# P11_RS2-32_RS-485.net
KiCad netlist of a schematic drawn in Altium Designer
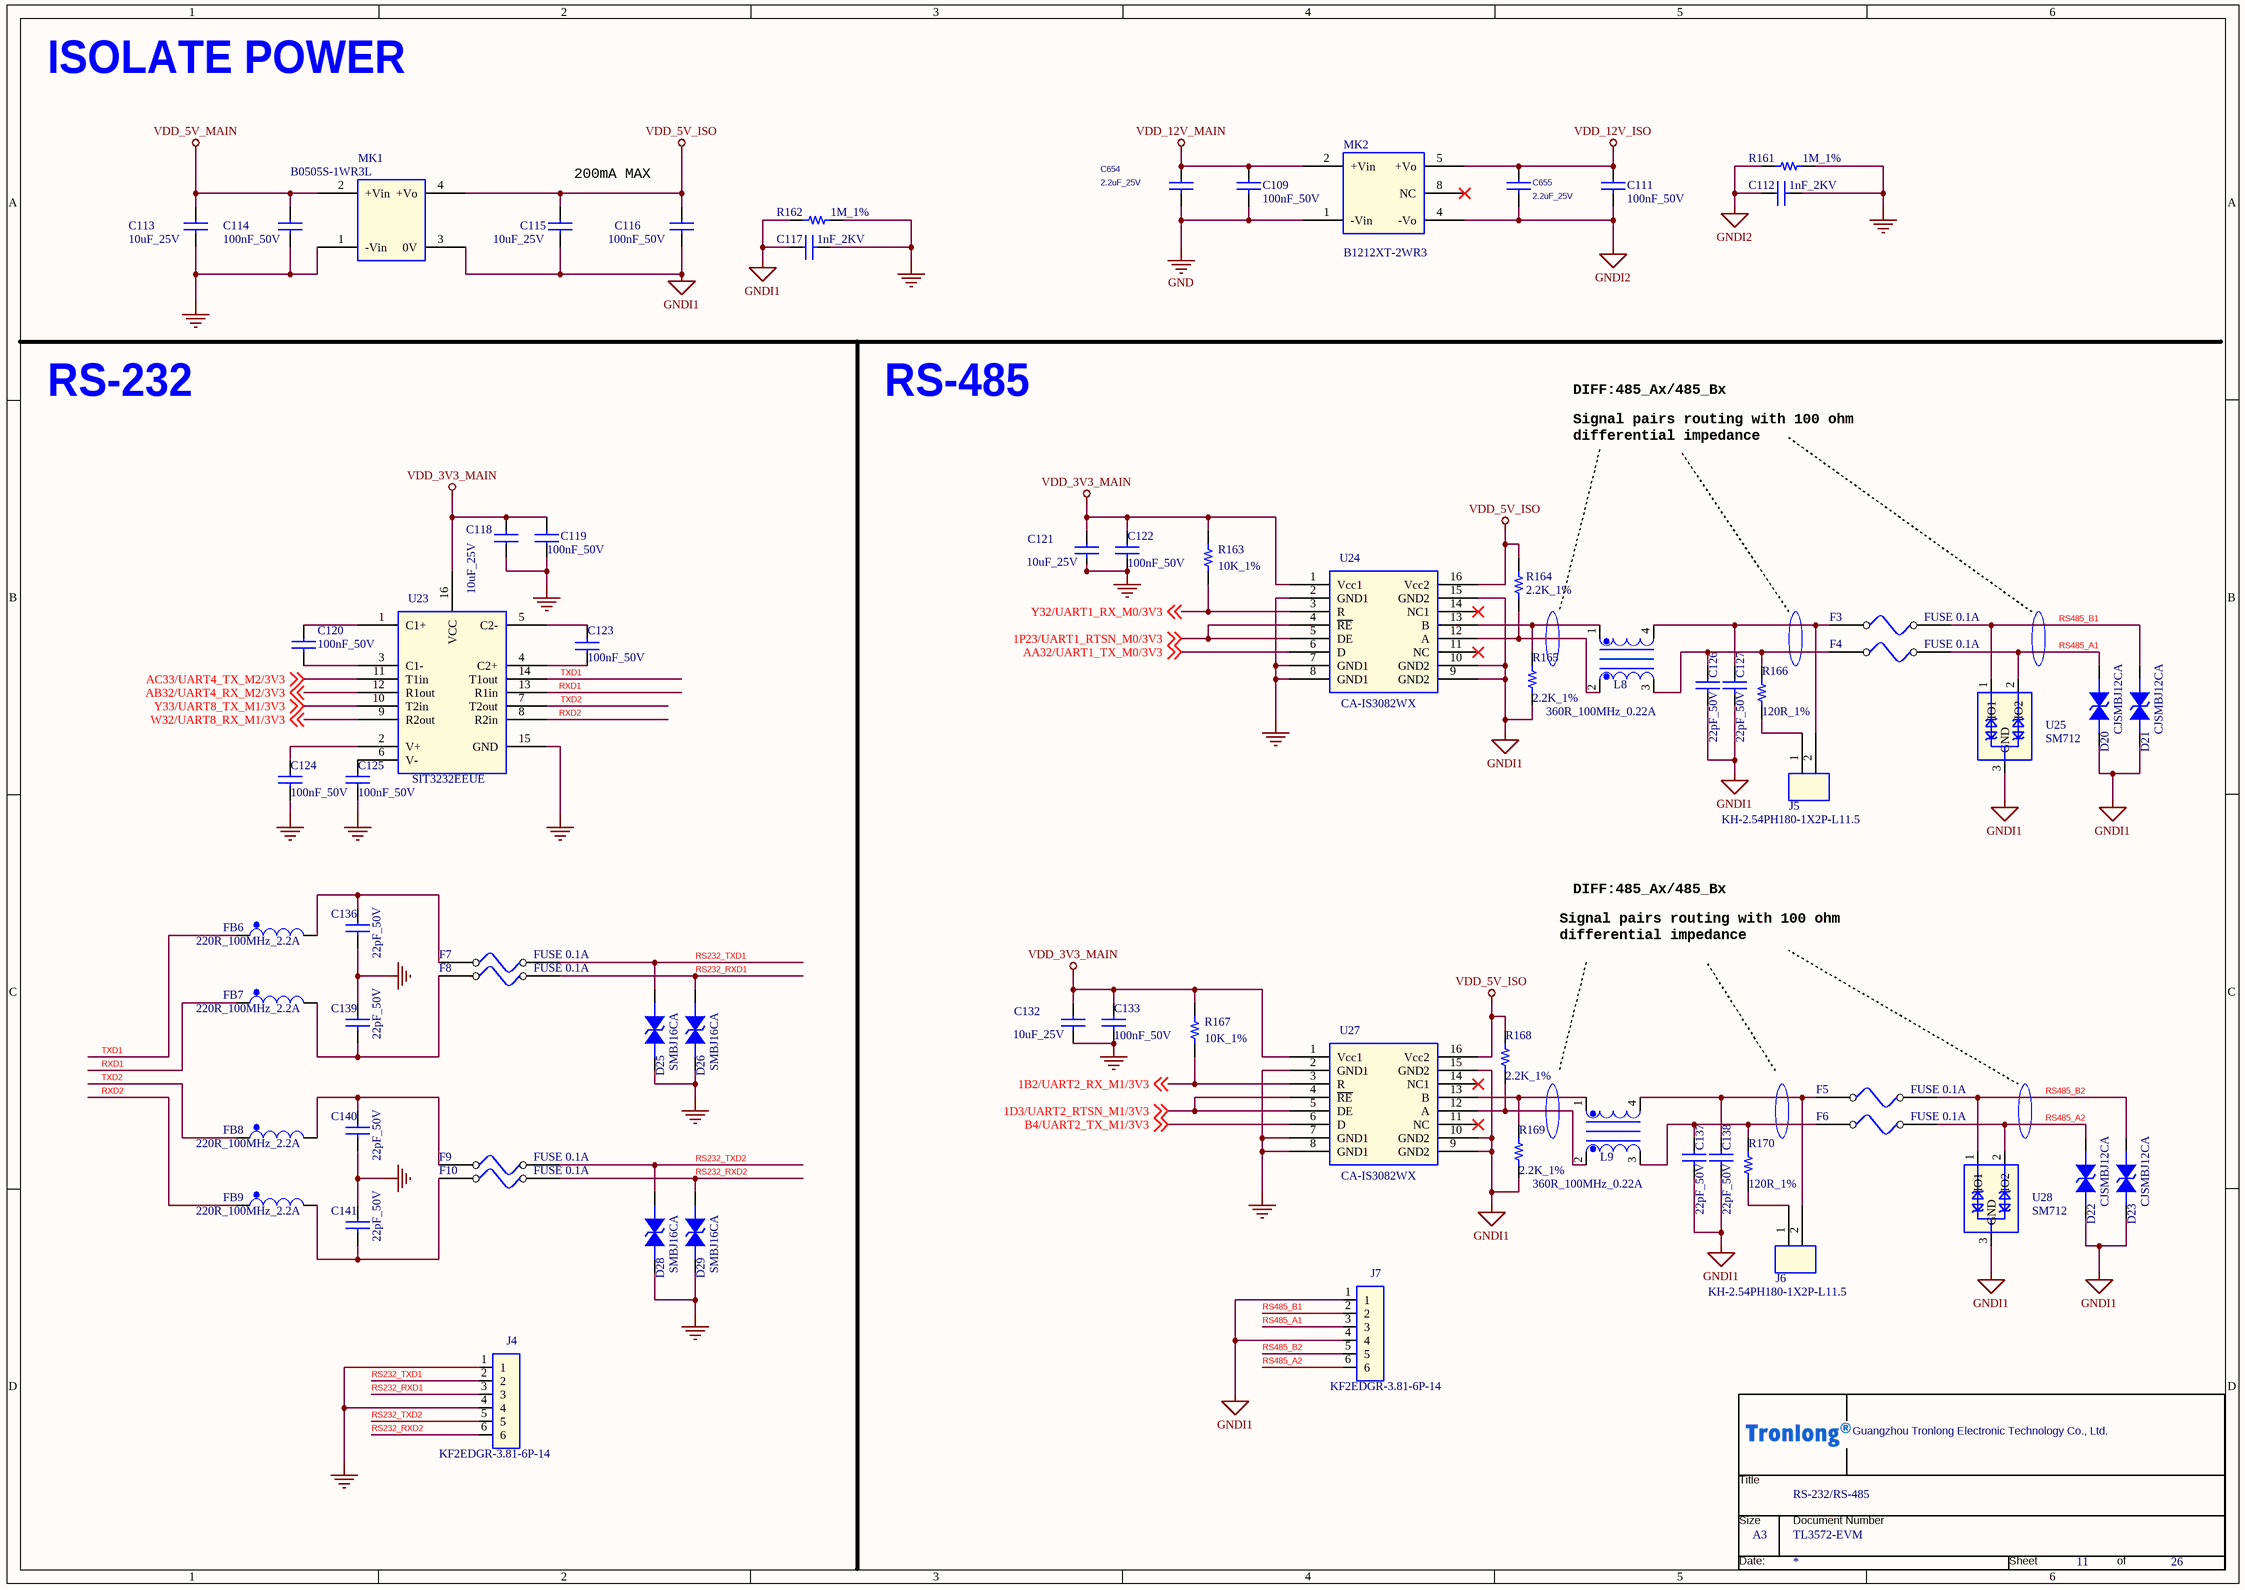
[diagram p0: P11_RS2-32_RS-485.SchDoc]

(export (version "E")
  (design (tool "Eeschema 10.0.6"))
  (components
    (comp (ref "*")
      (value "Tronlong_TITTLE_20211115")
      (fields
        (field (name "DOC") "TL3572-EVM")
        (field (name "TITLE") "RS-232/RS-485")
        (field (name "ORGNAME") "Guangzhou Tronlong Electronic Technology Co., Ltd.")
        (field (name "PAGE SIZE") "A3")
        (field (name "PAGE NUMBER") "11")
        (field (name "PAGE COUNT") "26")
      )
      (libsource (lib "*") (part "Tronlong_TITTLE_20211115"))
    )
    (comp (ref "C109")
      (value "100nF_50V")
      (footprint "C0402")
      (description "贴片陶瓷电容,100nF,10%,50V,X7R")
      (fields
        (field (name "MANUFACTURER") "广东风华高新科技股份有限公司（FH）")
        (field (name "MANUFACTURER PARTNUMBER") "0402B104K500NT")
      )
      (libsource (lib "*") (part "CAP NP_Dup2"))
    )
    (comp (ref "C111")
      (value "100nF_50V")
      (footprint "C0402")
      (description "贴片陶瓷电容,100nF,10%,50V,X7R")
      (fields
        (field (name "MANUFACTURER") "广东风华高新科技股份有限公司（FH）")
        (field (name "MANUFACTURER PARTNUMBER") "0402B104K500NT")
      )
      (libsource (lib "*") (part "CAP NP_Dup2"))
    )
    (comp (ref "C112")
      (value "1nF_2KV")
      (footprint "C1206")
      (description "贴片陶瓷电容,1nF,10%,2KV,X7R")
      (fields
        (field (name "MANUFACTURER") "广东风华高新科技股份有限公司（FH）")
        (field (name "MANUFACTURER PARTNUMBER") "1206B102K202NT")
      )
      (libsource (lib "*") (part "CAP NP_Dup2"))
    )
    (comp (ref "C113")
      (value "10uF_25V")
      (footprint "C0603")
      (description "贴片陶瓷电容,10uF,20%,25V,X5R")
      (fields
        (field (name "MANUFACTURER PARTNUMBER") "0603X106M250NT")
        (field (name "MANUFACTURER") "广东风华高新科技股份有限公司（FH）")
      )
      (libsource (lib "*") (part "CAP NP_Dup3"))
    )
    (comp (ref "C114")
      (value "100nF_50V")
      (footprint "C0402")
      (description "贴片陶瓷电容,100nF,10%,50V,X7R")
      (fields
        (field (name "MANUFACTURER PARTNUMBER") "0402B104K500NT")
        (field (name "MANUFACTURER") "广东风华高新科技股份有限公司（FH）")
      )
      (libsource (lib "*") (part "CAP NP_Dup3"))
    )
    (comp (ref "C115")
      (value "10uF_25V")
      (footprint "C0603")
      (description "贴片陶瓷电容,10uF,20%,25V,X5R")
      (fields
        (field (name "MANUFACTURER PARTNUMBER") "0603X106M250NT")
        (field (name "MANUFACTURER") "广东风华高新科技股份有限公司（FH）")
      )
      (libsource (lib "*") (part "CAP NP_Dup3"))
    )
    (comp (ref "C116")
      (value "100nF_50V")
      (footprint "C0402")
      (description "贴片陶瓷电容,100nF,10%,50V,X7R")
      (fields
        (field (name "MANUFACTURER") "广东风华高新科技股份有限公司（FH）")
        (field (name "MANUFACTURER PARTNUMBER") "0402B104K500NT")
      )
      (libsource (lib "*") (part "CAP NP_Dup3"))
    )
    (comp (ref "C117")
      (value "1nF_2KV")
      (footprint "C1206")
      (description "贴片陶瓷电容,1nF,10%,2KV,X7R")
      (fields
        (field (name "MANUFACTURER") "广东风华高新科技股份有限公司（FH）")
        (field (name "MANUFACTURER PARTNUMBER") "1206B102K202NT")
      )
      (libsource (lib "*") (part "CAP NP_Dup2"))
    )
    (comp (ref "C118")
      (value "10uF_25V")
      (footprint "C0603")
      (description "贴片陶瓷电容,10uF,20%,25V,X5R")
      (fields
        (field (name "MANUFACTURER") "广东风华高新科技股份有限公司（FH）")
        (field (name "MANUFACTURER PARTNUMBER") "0603X106M250NT")
      )
      (libsource (lib "*") (part "CAP NP_Dup2"))
    )
    (comp (ref "C119")
      (value "100nF_50V")
      (footprint "C0402")
      (description "贴片陶瓷电容,100nF,10%,50V,X7R")
      (fields
        (field (name "MANUFACTURER PARTNUMBER") "0402B104K500NT")
        (field (name "MANUFACTURER") "广东风华高新科技股份有限公司（FH）")
      )
      (libsource (lib "*") (part "CAP NP_Dup2"))
    )
    (comp (ref "C120")
      (value "100nF_50V")
      (footprint "C0402")
      (description "贴片陶瓷电容,100nF,10%,50V,X7R")
      (fields
        (field (name "MANUFACTURER PARTNUMBER") "0402B104K500NT")
        (field (name "MANUFACTURER") "广东风华高新科技股份有限公司（FH）")
      )
      (libsource (lib "*") (part "CAP NP_Dup2"))
    )
    (comp (ref "C121")
      (value "10uF_25V")
      (footprint "C0603")
      (description "贴片陶瓷电容,10uF,20%,25V,X5R")
      (fields
        (field (name "MANUFACTURER") "广东风华高新科技股份有限公司（FH）")
        (field (name "MANUFACTURER PARTNUMBER") "0603X106M250NT")
      )
      (libsource (lib "*") (part "CAP NP_Dup2"))
    )
    (comp (ref "C122")
      (value "100nF_50V")
      (footprint "C0402")
      (description "贴片陶瓷电容,100nF,10%,50V,X7R")
      (fields
        (field (name "MANUFACTURER") "广东风华高新科技股份有限公司（FH）")
        (field (name "MANUFACTURER PARTNUMBER") "0402B104K500NT")
      )
      (libsource (lib "*") (part "CAP NP_Dup2"))
    )
    (comp (ref "C123")
      (value "100nF_50V")
      (footprint "C0402")
      (description "贴片陶瓷电容,100nF,10%,50V,X7R")
      (fields
        (field (name "MANUFACTURER") "广东风华高新科技股份有限公司（FH）")
        (field (name "MANUFACTURER PARTNUMBER") "0402B104K500NT")
      )
      (libsource (lib "*") (part "CAP NP_Dup2"))
    )
    (comp (ref "C124")
      (value "100nF_50V")
      (footprint "C0402")
      (description "贴片陶瓷电容,100nF,10%,50V,X7R")
      (fields
        (field (name "MANUFACTURER") "广东风华高新科技股份有限公司（FH）")
        (field (name "MANUFACTURER PARTNUMBER") "0402B104K500NT")
      )
      (libsource (lib "*") (part "CAP NP_Dup2"))
    )
    (comp (ref "C125")
      (value "100nF_50V")
      (footprint "C0402")
      (description "贴片陶瓷电容,100nF,10%,50V,X7R")
      (fields
        (field (name "MANUFACTURER PARTNUMBER") "0402B104K500NT")
        (field (name "MANUFACTURER") "广东风华高新科技股份有限公司（FH）")
      )
      (libsource (lib "*") (part "CAP NP_Dup2"))
    )
    (comp (ref "C126")
      (value "22pF_50V")
      (footprint "C0603")
      (description "贴片陶瓷电容,22pF,5%,50V,COG")
      (fields
        (field (name "MANUFACTURER") "广东风华高新科技股份有限公司（FH）")
        (field (name "MANUFACTURER PARTNUMBER") "0603CG220J500NT")
      )
      (libsource (lib "*") (part "CAP NP_Dup2"))
    )
    (comp (ref "C127")
      (value "22pF_50V")
      (footprint "C0603")
      (description "贴片陶瓷电容,22pF,5%,50V,COG")
      (fields
        (field (name "MANUFACTURER PARTNUMBER") "0603CG220J500NT")
        (field (name "MANUFACTURER") "广东风华高新科技股份有限公司（FH）")
      )
      (libsource (lib "*") (part "CAP NP_Dup2"))
    )
    (comp (ref "C132")
      (value "10uF_25V")
      (footprint "C0603")
      (description "贴片陶瓷电容,10uF,20%,25V,X5R")
      (fields
        (field (name "MANUFACTURER") "广东风华高新科技股份有限公司（FH）")
        (field (name "MANUFACTURER PARTNUMBER") "0603X106M250NT")
      )
      (libsource (lib "*") (part "CAP NP_Dup2"))
    )
    (comp (ref "C133")
      (value "100nF_50V")
      (footprint "C0402")
      (description "贴片陶瓷电容,100nF,10%,50V,X7R")
      (fields
        (field (name "MANUFACTURER PARTNUMBER") "0402B104K500NT")
        (field (name "MANUFACTURER") "广东风华高新科技股份有限公司（FH）")
      )
      (libsource (lib "*") (part "CAP NP_Dup2"))
    )
    (comp (ref "C136")
      (value "22pF_50V")
      (footprint "C0603")
      (description "贴片陶瓷电容,22pF,5%,50V,C0G")
      (fields
        (field (name "MANUFACTURER PARTNUMBER") "0603CG220J500NT")
        (field (name "MANUFACTURER") "广东风华高新科技股份有限公司（FH）")
      )
      (libsource (lib "*") (part "CAP NP_Dup2"))
    )
    (comp (ref "C137")
      (value "22pF_50V")
      (footprint "C0603")
      (description "贴片陶瓷电容,22pF,5%,50V,COG")
      (fields
        (field (name "MANUFACTURER") "广东风华高新科技股份有限公司（FH）")
        (field (name "MANUFACTURER PARTNUMBER") "0603CG220J500NT")
      )
      (libsource (lib "*") (part "CAP NP_Dup2"))
    )
    (comp (ref "C138")
      (value "22pF_50V")
      (footprint "C0603")
      (description "贴片陶瓷电容,22pF,5%,50V,COG")
      (fields
        (field (name "MANUFACTURER PARTNUMBER") "0603CG220J500NT")
        (field (name "MANUFACTURER") "广东风华高新科技股份有限公司（FH）")
      )
      (libsource (lib "*") (part "CAP NP_Dup2"))
    )
    (comp (ref "C139")
      (value "22pF_50V")
      (footprint "C0603")
      (description "贴片陶瓷电容,22pF,5%,50V,C0G")
      (fields
        (field (name "MANUFACTURER") "广东风华高新科技股份有限公司（FH）")
        (field (name "MANUFACTURER PARTNUMBER") "0603CG220J500NT")
      )
      (libsource (lib "*") (part "CAP NP_Dup2"))
    )
    (comp (ref "C140")
      (value "22pF_50V")
      (footprint "C0603")
      (description "贴片陶瓷电容,22pF,5%,50V,C0G")
      (fields
        (field (name "MANUFACTURER PARTNUMBER") "0603CG220J500NT")
        (field (name "MANUFACTURER") "广东风华高新科技股份有限公司（FH）")
      )
      (libsource (lib "*") (part "CAP NP_Dup2"))
    )
    (comp (ref "C141")
      (value "22pF_50V")
      (footprint "C0603")
      (description "贴片陶瓷电容,22pF,5%,50V,C0G")
      (fields
        (field (name "MANUFACTURER") "广东风华高新科技股份有限公司（FH）")
        (field (name "MANUFACTURER PARTNUMBER") "0603CG220J500NT")
      )
      (libsource (lib "*") (part "CAP NP_Dup2"))
    )
    (comp (ref "C654")
      (value "2.2uF_25V")
      (footprint "C1206")
      (description "贴片陶瓷电容,2.2uF,10%,25V,X7R")
      (fields
        (field (name "MANUFACTURER PARTNUMBER") "1206B225K250NT")
        (field (name "MANUFACTURER") "广东风华高新科技股份有限公司（FH）")
      )
      (libsource (lib "*") (part "CAP NP_Dup2"))
    )
    (comp (ref "C655")
      (value "2.2uF_25V")
      (footprint "C1206")
      (description "贴片陶瓷电容,2.2uF,10%,25V,X7R")
      (fields
        (field (name "MANUFACTURER PARTNUMBER") "1206B225K250NT")
        (field (name "MANUFACTURER") "广东风华高新科技股份有限公司（FH）")
      )
      (libsource (lib "*") (part "CAP NP_Dup2"))
    )
    (comp (ref "D20")
      (value "CJSMBJ12CA")
      (footprint "SMB")
      (description "TVS二极管,VRWM=12V,VBR=13.35V,一组,双向")
      (fields (field (name "MANUFACTURER") "江苏长晶科技股份有限公司（JSCJ）"))
      (libsource (lib "*") (part "DIODE-TRIG"))
    )
    (comp (ref "D21")
      (value "CJSMBJ12CA")
      (footprint "SMB")
      (description "TVS二极管,VRWM=12V,VBR=13.35V,一组,双向")
      (fields (field (name "MANUFACTURER") "江苏长晶科技股份有限公司（JSCJ）"))
      (libsource (lib "*") (part "DIODE-TRIG"))
    )
    (comp (ref "D22")
      (value "CJSMBJ12CA")
      (footprint "SMB")
      (description "TVS二极管,VRWM=12V,VBR=13.35V,一组,双向")
      (fields (field (name "MANUFACTURER") "江苏长晶科技股份有限公司（JSCJ）"))
      (libsource (lib "*") (part "DIODE-TRIG"))
    )
    (comp (ref "D23")
      (value "CJSMBJ12CA")
      (footprint "SMB")
      (description "TVS二极管,VRWM=12V,VBR=13.35V,一组,双向")
      (fields (field (name "MANUFACTURER") "江苏长晶科技股份有限公司（JSCJ）"))
      (libsource (lib "*") (part "DIODE-TRIG"))
    )
    (comp (ref "D25")
      (value "SMBJ16CA")
      (footprint "SMB")
      (description "TVS二极管,VRWM=16V,VBR=17.8V,一组,双向")
      (fields (field (name "MANUFACTURER") "江苏长晶科技有限公司（JSCJ）"))
      (libsource (lib "*") (part "DIODE-TRIG"))
    )
    (comp (ref "D26")
      (value "SMBJ16CA")
      (footprint "SMB")
      (description "TVS二极管,VRWM=16V,VBR=17.8V,一组,双向")
      (fields (field (name "MANUFACTURER") "江苏长晶科技有限公司（JSCJ）"))
      (libsource (lib "*") (part "DIODE-TRIG"))
    )
    (comp (ref "D28")
      (value "SMBJ16CA")
      (footprint "SMB")
      (description "TVS二极管,VRWM=16V,VBR=17.8V,一组,双向")
      (fields (field (name "MANUFACTURER") "江苏长晶科技有限公司（JSCJ）"))
      (libsource (lib "*") (part "DIODE-TRIG"))
    )
    (comp (ref "D29")
      (value "SMBJ16CA")
      (footprint "SMB")
      (description "TVS二极管,VRWM=16V,VBR=17.8V,一组,双向")
      (fields (field (name "MANUFACTURER") "江苏长晶科技有限公司（JSCJ）"))
      (libsource (lib "*") (part "DIODE-TRIG"))
    )
    (comp (ref "F3")
      (value "FUSE 0.1A")
      (footprint "F0805")
      (description "自恢复保险丝,Vmax=24V,Imax=100A,Ihold=0.1A")
      (fields
        (field (name "MANUFACTURER") "东莞市竞沃电子科技有限公司（TLC）")
        (field (name "MANUFACTURER PARTNUMBER") "TLC-PSMD010/24")
      )
      (libsource (lib "*") (part "FUSE"))
    )
    (comp (ref "F4")
      (value "FUSE 0.1A")
      (footprint "F0805")
      (description "自恢复保险丝,Vmax=24V,Imax=100A,Ihold=0.1A")
      (fields
        (field (name "MANUFACTURER PARTNUMBER") "TLC-PSMD010/24")
        (field (name "MANUFACTURER") "东莞市竞沃电子科技有限公司（TLC）")
      )
      (libsource (lib "*") (part "FUSE"))
    )
    (comp (ref "F5")
      (value "FUSE 0.1A")
      (footprint "F0805")
      (description "自恢复保险丝,Vmax=24V,Imax=100A,Ihold=0.1A")
      (fields
        (field (name "MANUFACTURER") "东莞市竞沃电子科技有限公司（TLC）")
        (field (name "MANUFACTURER PARTNUMBER") "TLC-PSMD010/24")
      )
      (libsource (lib "*") (part "FUSE"))
    )
    (comp (ref "F6")
      (value "FUSE 0.1A")
      (footprint "F0805")
      (description "自恢复保险丝,Vmax=24V,Imax=100A,Ihold=0.1A")
      (fields
        (field (name "MANUFACTURER PARTNUMBER") "TLC-PSMD010/24")
        (field (name "MANUFACTURER") "东莞市竞沃电子科技有限公司（TLC）")
      )
      (libsource (lib "*") (part "FUSE"))
    )
    (comp (ref "F7")
      (value "FUSE 0.1A")
      (footprint "F0805")
      (description "自恢复保险丝,Vmax=24V,Imax=100A,Ihold=0.1A")
      (fields
        (field (name "MANUFACTURER") "东莞市竞沃电子科技有限公司（TLC）")
        (field (name "MANUFACTURER PARTNUMBER") "TLC-PSMD010/24")
      )
      (libsource (lib "*") (part "FUSE"))
    )
    (comp (ref "F8")
      (value "FUSE 0.1A")
      (footprint "F0805")
      (description "自恢复保险丝,Vmax=24V,Imax=100A,Ihold=0.1A")
      (fields
        (field (name "MANUFACTURER") "东莞市竞沃电子科技有限公司（TLC）")
        (field (name "MANUFACTURER PARTNUMBER") "TLC-PSMD010/24")
      )
      (libsource (lib "*") (part "FUSE"))
    )
    (comp (ref "F9")
      (value "FUSE 0.1A")
      (footprint "F0805")
      (description "自恢复保险丝,Vmax=24V,Imax=100A,Ihold=0.1A")
      (fields
        (field (name "MANUFACTURER") "东莞市竞沃电子科技有限公司（TLC）")
        (field (name "MANUFACTURER PARTNUMBER") "TLC-PSMD010/24")
      )
      (libsource (lib "*") (part "FUSE"))
    )
    (comp (ref "F10")
      (value "FUSE 0.1A")
      (footprint "F0805")
      (description "自恢复保险丝,Vmax=24V,Imax=100A,Ihold=0.1A")
      (fields
        (field (name "MANUFACTURER") "东莞市竞沃电子科技有限公司（TLC）")
        (field (name "MANUFACTURER PARTNUMBER") "TLC-PSMD010/24")
      )
      (libsource (lib "*") (part "FUSE"))
    )
    (comp (ref "FB6")
      (value "220R_100MHz_2.2A")
      (footprint "L0603")
      (description "磁珠,50mΩ,2.2A,220R@100MHz")
      (fields
        (field (name "MANUFACTURER") "深圳顺络电子股份有限公司（Sunlord）")
        (field (name "MANUFACTURER PARTNUMBER") "UPZ1608U221-2R2TF")
      )
      (libsource (lib "*") (part "FB_0"))
    )
    (comp (ref "FB7")
      (value "220R_100MHz_2.2A")
      (footprint "L0603")
      (description "磁珠,50mΩ,2.2A,220R@100MHz")
      (fields
        (field (name "MANUFACTURER PARTNUMBER") "UPZ1608U221-2R2TF")
        (field (name "MANUFACTURER") "深圳顺络电子股份有限公司（Sunlord）")
      )
      (libsource (lib "*") (part "FB_0"))
    )
    (comp (ref "FB8")
      (value "220R_100MHz_2.2A")
      (footprint "L0603")
      (description "磁珠,50mΩ,2.2A,220R@100MHz")
      (fields
        (field (name "MANUFACTURER PARTNUMBER") "UPZ1608U221-2R2TF")
        (field (name "MANUFACTURER") "深圳顺络电子股份有限公司（Sunlord）")
      )
      (libsource (lib "*") (part "FB_0"))
    )
    (comp (ref "FB9")
      (value "220R_100MHz_2.2A")
      (footprint "L0603")
      (description "磁珠,50mΩ,2.2A,220R@100MHz")
      (fields
        (field (name "MANUFACTURER") "深圳顺络电子股份有限公司（Sunlord）")
        (field (name "MANUFACTURER PARTNUMBER") "UPZ1608U221-2R2TF")
      )
      (libsource (lib "*") (part "FB_0"))
    )
    (comp (ref "J4")
      (value "KF2EDGR-3.81-6P-14")
      (footprint "kf2eg_3_81-6p")
      (description "插拔式端子座,1x6P,3.81mm,90度")
      (fields (field (name "MANUFACTURER") "慈溪市科发电子有限公司（KEFA）"))
      (libsource (lib "*") (part "CON6"))
    )
    (comp (ref "J5")
      (value "KH-2.54PH180-1X2P-L11.5")
      (footprint "header_1x2p_2d54_male")
      (description "插件单排排针,1x2P,2.54mm,180度")
      (fields (field (name "MANUFACTURER") "深圳市金航标电子有限公司(kinghelm)"))
      (libsource (lib "*") (part "CON2_0"))
    )
    (comp (ref "J6")
      (value "KH-2.54PH180-1X2P-L11.5")
      (footprint "header_1x2p_2d54_male")
      (description "插件单排排针,1x2P,2.54mm,180度")
      (fields (field (name "MANUFACTURER") "深圳市金航标电子有限公司(kinghelm)"))
      (libsource (lib "*") (part "CON2_0"))
    )
    (comp (ref "J7")
      (value "KF2EDGR-3.81-6P-14")
      (footprint "kf2eg_3_81-6p")
      (description "插拔式端子座,1x6P,3.81mm,90度")
      (fields (field (name "MANUFACTURER") "慈溪市科发电子有限公司（KEFA）"))
      (libsource (lib "*") (part "CON6"))
    )
    (comp (ref "L8")
      (value "360R_100MHz_0.22A")
      (footprint "SMD-L2012M-4P")
      (description "贴片共模电感,500mΩ,0.22A,50V,360Ω@100MHz")
      (fields
        (field (name "MANUFACTURER PARTNUMBER") "ACM2012-361-2P-T001")
        (field (name "MANUFACTURER") "TDK(日本东电化)")
      )
      (libsource (lib "*") (part "TFR_AXA_A_1"))
    )
    (comp (ref "L9")
      (value "360R_100MHz_0.22A")
      (footprint "SMD-L2012M-4P")
      (description "贴片共模电感,500mΩ,0.22A,50V,360Ω@100MHz")
      (fields
        (field (name "MANUFACTURER") "TDK(日本东电化)")
        (field (name "MANUFACTURER PARTNUMBER") "ACM2012-361-2P-T001")
      )
      (libsource (lib "*") (part "TFR_AXA_A_1"))
    )
    (comp (ref "MK1")
      (value "B0505S-1WR3L")
      (footprint "PW_4P_2D54_L116W60_180_DIP")
      (description "DC-DC隔离电源,Vi=5V,Vo=5V,Io=200mA,3KV,η=77%,插件")
      (fields (field (name "MANUFACTURER") "广州金升阳科技有限公司（MORNSUN）"))
      (libsource (lib "*") (part "B_S-2W_1"))
    )
    (comp (ref "MK2")
      (value "B1212XT-2WR3")
      (footprint "PWRM_SMD_5P_L132W85_P254_LS114")
      (description "DC-DC隔离电源,Vi=12V,Vo=12V,Io=167mA,1.5KV,η=80%,贴片")
      (fields (field (name "MANUFACTURER") "广州金升阳科技有限公司（MORNSUN）"))
      (libsource (lib "*") (part "B_S-2W_2"))
    )
    (comp (ref "R161")
      (value "1M_1%")
      (footprint "R1206")
      (description "贴片电阻,1M,±1%,1/4W")
      (fields
        (field (name "MANUFACTURER") "广东风华高新科技股份有限公司（FH）")
        (field (name "MANUFACTURER PARTNUMBER") "RS-06K1004FT")
      )
      (libsource (lib "*") (part "Resistor"))
    )
    (comp (ref "R162")
      (value "1M_1%")
      (footprint "R1206")
      (description "贴片电阻,1M,±1%,1/4W")
      (fields
        (field (name "MANUFACTURER") "广东风华高新科技股份有限公司（FH）")
        (field (name "MANUFACTURER PARTNUMBER") "RS-06K1004FT")
      )
      (libsource (lib "*") (part "Resistor"))
    )
    (comp (ref "R163")
      (value "10K_1%")
      (footprint "R0402")
      (description "贴片电阻,10K,±1%,1/16W")
      (fields
        (field (name "MANUFACTURER") "广东风华高新科技股份有限公司（FH）")
        (field (name "MANUFACTURER PARTNUMBER") "RC-02K1002FT")
      )
      (libsource (lib "*") (part "Resistor_Dup3"))
    )
    (comp (ref "R164")
      (value "2.2K_1%")
      (footprint "R0603")
      (description "贴片电阻,2.2K,±1%,1/10W")
      (fields
        (field (name "MANUFACTURER PARTNUMBER") "RS-03K2201FT")
        (field (name "MANUFACTURER") "广东风华高新科技股份有限公司（FH）")
      )
      (libsource (lib "*") (part "Resistor_Dup3"))
    )
    (comp (ref "R165")
      (value "2.2K_1%")
      (footprint "R0603")
      (description "贴片电阻,2.2K,±1%,1/10W")
      (fields
        (field (name "MANUFACTURER") "广东风华高新科技股份有限公司（FH）")
        (field (name "MANUFACTURER PARTNUMBER") "RS-03K2201FT")
      )
      (libsource (lib "*") (part "Resistor_Dup3"))
    )
    (comp (ref "R166")
      (value "120R_1%")
      (footprint "R0805")
      (description "贴片电阻,120R,±1%,1/8W")
      (fields
        (field (name "MANUFACTURER") "广东风华高新科技股份有限公司（FH）")
        (field (name "MANUFACTURER PARTNUMBER") "RS-05K1200FT")
      )
      (libsource (lib "*") (part "Resistor_Dup3"))
    )
    (comp (ref "R167")
      (value "10K_1%")
      (footprint "R0402")
      (description "贴片电阻,10K,±1%,1/16W")
      (fields
        (field (name "MANUFACTURER") "广东风华高新科技股份有限公司（FH）")
        (field (name "MANUFACTURER PARTNUMBER") "RC-02K1002FT")
      )
      (libsource (lib "*") (part "Resistor_Dup3"))
    )
    (comp (ref "R168")
      (value "2.2K_1%")
      (footprint "R0603")
      (description "贴片电阻,2.2K,±1%,1/10W")
      (fields
        (field (name "MANUFACTURER PARTNUMBER") "RS-03K2201FT")
        (field (name "MANUFACTURER") "广东风华高新科技股份有限公司（FH）")
      )
      (libsource (lib "*") (part "Resistor_Dup3"))
    )
    (comp (ref "R169")
      (value "2.2K_1%")
      (footprint "R0603")
      (description "贴片电阻,2.2K,±1%,1/10W")
      (fields
        (field (name "MANUFACTURER PARTNUMBER") "RS-03K2201FT")
        (field (name "MANUFACTURER") "广东风华高新科技股份有限公司（FH）")
      )
      (libsource (lib "*") (part "Resistor_Dup3"))
    )
    (comp (ref "R170")
      (value "120R_1%")
      (footprint "R0805")
      (description "贴片电阻,120R,±1%,1/8W")
      (fields
        (field (name "MANUFACTURER") "广东风华高新科技股份有限公司（FH）")
        (field (name "MANUFACTURER PARTNUMBER") "RS-05K1200FT")
      )
      (libsource (lib "*") (part "Resistor_Dup3"))
    )
    (comp (ref "U23")
      (value "SIT3232EEUE")
      (footprint "TSSOP16_PW16")
      (description "RS232收发器")
      (fields (field (name "MANUFACTURER") "湖南芯力特电子科技有限公司（SIT）"))
      (libsource (lib "*") (part "MAX232A_0"))
    )
    (comp (ref "U24")
      (value "CA-IS3082WX")
      (footprint "SO16W")
      (description "RS485收发器,2.5V~5.5V")
      (fields (field (name "MANUFACTURER") "上海川土微电子有限公司（CHIPANALOG）"))
      (libsource (lib "*") (part "ISO3082_4"))
    )
    (comp (ref "U25")
      (value "SM712")
      (footprint "SOT23-3")
      (description "TVS二极管,VRWM=7V/12V,VBR=7.5V/13.3V,两组,双向,30KV,30KV")
      (fields (field (name "MANUFACTURER") "上海雷卯电子科技有限公司（Leiditech）"))
      (libsource (lib "*") (part "PSM712"))
    )
    (comp (ref "U27")
      (value "CA-IS3082WX")
      (footprint "SO16W")
      (description "RS485收发器,2.5V~5.5V")
      (fields (field (name "MANUFACTURER") "上海川土微电子有限公司（CHIPANALOG）"))
      (libsource (lib "*") (part "ISO3082_5"))
    )
    (comp (ref "U28")
      (value "SM712")
      (footprint "SOT23-3")
      (description "TVS二极管,VRWM=7V/12V,VBR=7.5V/13.3V,两组,双向,30KV,30KV")
      (fields (field (name "MANUFACTURER") "上海雷卯电子科技有限公司（Leiditech）"))
      (libsource (lib "*") (part "PSM712"))
    )
  )
  (nets
    (net (code "1") (name "/RS232_RXD1") (class "Default")
      (node (ref "D26") (pin "2") (pinfunction "2_2") (pintype "passive"))
      (node (ref "F8") (pin "2") (pinfunction "2_2") (pintype "passive"))
      (node (ref "J4") (pin "3") (pinfunction "3_3") (pintype "passive"))
    )
    (net (code "2") (name "/RS232_RXD2") (class "Default")
      (node (ref "D29") (pin "2") (pinfunction "2_2") (pintype "passive"))
      (node (ref "F10") (pin "2") (pinfunction "2_2") (pintype "passive"))
      (node (ref "J4") (pin "6") (pinfunction "6_6") (pintype "passive"))
    )
    (net (code "3") (name "/RS232_TXD1") (class "Default")
      (node (ref "D25") (pin "2") (pinfunction "2_2") (pintype "passive"))
      (node (ref "F7") (pin "2") (pinfunction "2_2") (pintype "passive"))
      (node (ref "J4") (pin "2") (pinfunction "2_2") (pintype "passive"))
    )
    (net (code "4") (name "/RS232_TXD2") (class "Default")
      (node (ref "D28") (pin "2") (pinfunction "2_2") (pintype "passive"))
      (node (ref "F9") (pin "2") (pinfunction "2_2") (pintype "passive"))
      (node (ref "J4") (pin "5") (pinfunction "5_5") (pintype "passive"))
    )
    (net (code "5") (name "/RS485_A1") (class "Default")
      (node (ref "D20") (pin "2") (pinfunction "2_2") (pintype "passive"))
      (node (ref "F4") (pin "2") (pinfunction "2_2") (pintype "passive"))
      (node (ref "J7") (pin "3") (pinfunction "3_3") (pintype "passive"))
      (node (ref "U25") (pin "2") (pinfunction "IO2_2") (pintype "passive"))
    )
    (net (code "6") (name "/RS485_A2") (class "Default")
      (node (ref "D22") (pin "2") (pinfunction "2_2") (pintype "passive"))
      (node (ref "F6") (pin "2") (pinfunction "2_2") (pintype "passive"))
      (node (ref "J7") (pin "6") (pinfunction "6_6") (pintype "passive"))
      (node (ref "U28") (pin "2") (pinfunction "IO2_2") (pintype "passive"))
    )
    (net (code "7") (name "/RS485_B1") (class "Default")
      (node (ref "D21") (pin "2") (pinfunction "2_2") (pintype "passive"))
      (node (ref "F3") (pin "2") (pinfunction "2_2") (pintype "passive"))
      (node (ref "J7") (pin "2") (pinfunction "2_2") (pintype "passive"))
      (node (ref "U25") (pin "1") (pinfunction "IO1_1") (pintype "passive"))
    )
    (net (code "8") (name "/RS485_B2") (class "Default")
      (node (ref "D23") (pin "2") (pinfunction "2_2") (pintype "passive"))
      (node (ref "F5") (pin "2") (pinfunction "2_2") (pintype "passive"))
      (node (ref "J7") (pin "5") (pinfunction "5_5") (pintype "passive"))
      (node (ref "U28") (pin "1") (pinfunction "IO1_1") (pintype "passive"))
    )
    (net (code "9") (name "/RXD1") (class "Default")
      (node (ref "FB7") (pin "1") (pinfunction "1_1") (pintype "passive"))
      (node (ref "U23") (pin "13") (pinfunction "R1in_13") (pintype "passive"))
    )
    (net (code "10") (name "/RXD2") (class "Default")
      (node (ref "FB9") (pin "1") (pinfunction "1_1") (pintype "passive"))
      (node (ref "U23") (pin "8") (pinfunction "R2in_8") (pintype "passive"))
    )
    (net (code "11") (name "/TXD1") (class "Default")
      (node (ref "FB6") (pin "1") (pinfunction "1_1") (pintype "passive"))
      (node (ref "U23") (pin "14") (pinfunction "T1out_14") (pintype "passive"))
    )
    (net (code "12") (name "/TXD2") (class "Default")
      (node (ref "FB8") (pin "1") (pinfunction "1_1") (pintype "passive"))
      (node (ref "U23") (pin "7") (pinfunction "T2out_7") (pintype "passive"))
    )
    (net (code "13") (name "1B2{slash}UART2_RX_M1{slash}3V3") (class "Default")
      (node (ref "R167") (pin "2") (pinfunction "2_2") (pintype "passive"))
      (node (ref "U27") (pin "3") (pinfunction "R_3") (pintype "passive"))
    )
    (net (code "14") (name "1D3{slash}UART2_RTSN_M1{slash}3V3") (class "Default")
      (node (ref "U27") (pin "4") (pinfunction "~{RE}_4") (pintype "passive"))
      (node (ref "U27") (pin "5") (pinfunction "DE_5") (pintype "passive"))
    )
    (net (code "15") (name "1P23{slash}UART1_RTSN_M0{slash}3V3") (class "Default")
      (node (ref "U24") (pin "4") (pinfunction "~{RE}_4") (pintype "passive"))
      (node (ref "U24") (pin "5") (pinfunction "DE_5") (pintype "passive"))
    )
    (net (code "16") (name "AA32{slash}UART1_TX_M0{slash}3V3") (class "Default")
      (node (ref "U24") (pin "6") (pinfunction "D_6") (pintype "passive"))
    )
    (net (code "17") (name "AB32{slash}UART4_RX_M2{slash}3V3") (class "Default")
      (node (ref "U23") (pin "12") (pinfunction "R1out_12") (pintype "passive"))
    )
    (net (code "18") (name "AC33{slash}UART4_TX_M2{slash}3V3") (class "Default")
      (node (ref "U23") (pin "11") (pinfunction "T1in_11") (pintype "passive"))
    )
    (net (code "19") (name "B4{slash}UART2_TX_M1{slash}3V3") (class "Default")
      (node (ref "U27") (pin "6") (pinfunction "D_6") (pintype "passive"))
    )
    (net (code "20") (name "GND") (class "Default")
      (node (ref "C109") (pin "2") (pinfunction "2_2") (pintype "passive"))
      (node (ref "C112") (pin "2") (pinfunction "2_2") (pintype "passive"))
      (node (ref "C113") (pin "2") (pinfunction "2_2") (pintype "passive"))
      (node (ref "C114") (pin "2") (pinfunction "2_2") (pintype "passive"))
      (node (ref "C117") (pin "2") (pinfunction "2_2") (pintype "passive"))
      (node (ref "C118") (pin "1") (pinfunction "1_1") (pintype "passive"))
      (node (ref "C119") (pin "1") (pinfunction "1_1") (pintype "passive"))
      (node (ref "C121") (pin "2") (pinfunction "2_2") (pintype "passive"))
      (node (ref "C122") (pin "2") (pinfunction "2_2") (pintype "passive"))
      (node (ref "C124") (pin "2") (pinfunction "2_2") (pintype "passive"))
      (node (ref "C125") (pin "2") (pinfunction "2_2") (pintype "passive"))
      (node (ref "C132") (pin "2") (pinfunction "2_2") (pintype "passive"))
      (node (ref "C133") (pin "2") (pinfunction "2_2") (pintype "passive"))
      (node (ref "C136") (pin "2") (pinfunction "2_2") (pintype "passive"))
      (node (ref "C139") (pin "1") (pinfunction "1_1") (pintype "passive"))
      (node (ref "C140") (pin "2") (pinfunction "2_2") (pintype "passive"))
      (node (ref "C141") (pin "1") (pinfunction "1_1") (pintype "passive"))
      (node (ref "C654") (pin "2") (pinfunction "2_2") (pintype "passive"))
      (node (ref "D25") (pin "1") (pinfunction "1_1") (pintype "passive"))
      (node (ref "D26") (pin "1") (pinfunction "1_1") (pintype "passive"))
      (node (ref "D28") (pin "1") (pinfunction "1_1") (pintype "passive"))
      (node (ref "D29") (pin "1") (pinfunction "1_1") (pintype "passive"))
      (node (ref "J4") (pin "1") (pinfunction "1_1") (pintype "passive"))
      (node (ref "J4") (pin "4") (pinfunction "4_4") (pintype "passive"))
      (node (ref "MK1") (pin "1") (pinfunction "-Vin_1") (pintype "passive"))
      (node (ref "MK2") (pin "1") (pinfunction "-Vin_1") (pintype "passive"))
      (node (ref "R161") (pin "2") (pinfunction "2_2") (pintype "passive"))
      (node (ref "R162") (pin "2") (pinfunction "2_2") (pintype "passive"))
      (node (ref "U23") (pin "15") (pinfunction "GND_15") (pintype "passive"))
      (node (ref "U24") (pin "2") (pinfunction "GND1_2") (pintype "power_in"))
      (node (ref "U24") (pin "7") (pinfunction "GND1_7") (pintype "power_in"))
      (node (ref "U24") (pin "8") (pinfunction "GND1_8") (pintype "power_in"))
      (node (ref "U27") (pin "2") (pinfunction "GND1_2") (pintype "power_in"))
      (node (ref "U27") (pin "7") (pinfunction "GND1_7") (pintype "power_in"))
      (node (ref "U27") (pin "8") (pinfunction "GND1_8") (pintype "power_in"))
    )
    (net (code "21") (name "GNDI1") (class "Default")
      (node (ref "C115") (pin "2") (pinfunction "2_2") (pintype "passive"))
      (node (ref "C116") (pin "2") (pinfunction "2_2") (pintype "passive"))
      (node (ref "C117") (pin "1") (pinfunction "1_1") (pintype "passive"))
      (node (ref "C126") (pin "2") (pinfunction "2_2") (pintype "passive"))
      (node (ref "C127") (pin "2") (pinfunction "2_2") (pintype "passive"))
      (node (ref "C137") (pin "2") (pinfunction "2_2") (pintype "passive"))
      (node (ref "C138") (pin "2") (pinfunction "2_2") (pintype "passive"))
      (node (ref "D20") (pin "1") (pinfunction "1_1") (pintype "passive"))
      (node (ref "D21") (pin "1") (pinfunction "1_1") (pintype "passive"))
      (node (ref "D22") (pin "1") (pinfunction "1_1") (pintype "passive"))
      (node (ref "D23") (pin "1") (pinfunction "1_1") (pintype "passive"))
      (node (ref "J7") (pin "1") (pinfunction "1_1") (pintype "passive"))
      (node (ref "J7") (pin "4") (pinfunction "4_4") (pintype "passive"))
      (node (ref "MK1") (pin "3") (pinfunction "0V_3") (pintype "passive"))
      (node (ref "R162") (pin "1") (pinfunction "1_1") (pintype "passive"))
      (node (ref "R165") (pin "2") (pinfunction "2_2") (pintype "passive"))
      (node (ref "R169") (pin "2") (pinfunction "2_2") (pintype "passive"))
      (node (ref "U24") (pin "10") (pinfunction "GND2_10") (pintype "power_in"))
      (node (ref "U24") (pin "15") (pinfunction "GND2_15") (pintype "power_in"))
      (node (ref "U24") (pin "9") (pinfunction "GND2_9") (pintype "power_in"))
      (node (ref "U25") (pin "3") (pinfunction "GND_3") (pintype "passive"))
      (node (ref "U27") (pin "10") (pinfunction "GND2_10") (pintype "power_in"))
      (node (ref "U27") (pin "15") (pinfunction "GND2_15") (pintype "power_in"))
      (node (ref "U27") (pin "9") (pinfunction "GND2_9") (pintype "power_in"))
      (node (ref "U28") (pin "3") (pinfunction "GND_3") (pintype "passive"))
    )
    (net (code "22") (name "GNDI2") (class "Default")
      (node (ref "C111") (pin "2") (pinfunction "2_2") (pintype "passive"))
      (node (ref "C112") (pin "1") (pinfunction "1_1") (pintype "passive"))
      (node (ref "C655") (pin "2") (pinfunction "2_2") (pintype "passive"))
      (node (ref "MK2") (pin "4") (pinfunction "-Vo_4") (pintype "passive"))
      (node (ref "R161") (pin "1") (pinfunction "1_1") (pintype "passive"))
    )
    (net (code "23") (name "Net-(C126-Pad1)") (class "Default")
      (node (ref "C126") (pin "1") (pinfunction "1_1") (pintype "passive"))
      (node (ref "F4") (pin "1") (pinfunction "1_1") (pintype "passive"))
      (node (ref "L8") (pin "3") (pinfunction "3_3") (pintype "passive"))
      (node (ref "R166") (pin "2") (pinfunction "2_2") (pintype "passive"))
    )
    (net (code "24") (name "Net-(C127-Pad1)") (class "Default")
      (node (ref "C127") (pin "1") (pinfunction "1_1") (pintype "passive"))
      (node (ref "F3") (pin "1") (pinfunction "1_1") (pintype "passive"))
      (node (ref "J5") (pin "2") (pinfunction "2_2") (pintype "passive"))
      (node (ref "L8") (pin "4") (pinfunction "4_4") (pintype "passive"))
    )
    (net (code "25") (name "Net-(C136-Pad1)") (class "Default")
      (node (ref "C136") (pin "1") (pinfunction "1_1") (pintype "passive"))
      (node (ref "F7") (pin "1") (pinfunction "1_1") (pintype "passive"))
      (node (ref "FB6") (pin "2") (pinfunction "2_2") (pintype "passive"))
    )
    (net (code "26") (name "Net-(C137-Pad1)") (class "Default")
      (node (ref "C137") (pin "1") (pinfunction "1_1") (pintype "passive"))
      (node (ref "F6") (pin "1") (pinfunction "1_1") (pintype "passive"))
      (node (ref "L9") (pin "3") (pinfunction "3_3") (pintype "passive"))
      (node (ref "R170") (pin "2") (pinfunction "2_2") (pintype "passive"))
    )
    (net (code "27") (name "Net-(C138-Pad1)") (class "Default")
      (node (ref "C138") (pin "1") (pinfunction "1_1") (pintype "passive"))
      (node (ref "F5") (pin "1") (pinfunction "1_1") (pintype "passive"))
      (node (ref "J6") (pin "2") (pinfunction "2_2") (pintype "passive"))
      (node (ref "L9") (pin "4") (pinfunction "4_4") (pintype "passive"))
    )
    (net (code "28") (name "Net-(C139-Pad2)") (class "Default")
      (node (ref "C139") (pin "2") (pinfunction "2_2") (pintype "passive"))
      (node (ref "F8") (pin "1") (pinfunction "1_1") (pintype "passive"))
      (node (ref "FB7") (pin "2") (pinfunction "2_2") (pintype "passive"))
    )
    (net (code "29") (name "Net-(C140-Pad1)") (class "Default")
      (node (ref "C140") (pin "1") (pinfunction "1_1") (pintype "passive"))
      (node (ref "F9") (pin "1") (pinfunction "1_1") (pintype "passive"))
      (node (ref "FB8") (pin "2") (pinfunction "2_2") (pintype "passive"))
    )
    (net (code "30") (name "Net-(C141-Pad2)") (class "Default")
      (node (ref "C141") (pin "2") (pinfunction "2_2") (pintype "passive"))
      (node (ref "F10") (pin "1") (pinfunction "1_1") (pintype "passive"))
      (node (ref "FB9") (pin "2") (pinfunction "2_2") (pintype "passive"))
    )
    (net (code "31") (name "Net-(J5-Pad1)") (class "Default")
      (node (ref "J5") (pin "1") (pinfunction "1_1") (pintype "passive"))
      (node (ref "R166") (pin "1") (pinfunction "1_1") (pintype "passive"))
    )
    (net (code "32") (name "Net-(J6-Pad1)") (class "Default")
      (node (ref "J6") (pin "1") (pinfunction "1_1") (pintype "passive"))
      (node (ref "R170") (pin "1") (pinfunction "1_1") (pintype "passive"))
    )
    (net (code "33") (name "Net-(U23-C1+)") (class "Default")
      (node (ref "C120") (pin "1") (pinfunction "1_1") (pintype "passive"))
      (node (ref "U23") (pin "1") (pinfunction "C1+_1") (pintype "passive"))
    )
    (net (code "34") (name "Net-(U23-C1-)") (class "Default")
      (node (ref "C120") (pin "2") (pinfunction "2_2") (pintype "passive"))
      (node (ref "U23") (pin "3") (pinfunction "C1-_3") (pintype "passive"))
    )
    (net (code "35") (name "Net-(U23-C2+)") (class "Default")
      (node (ref "C123") (pin "1") (pinfunction "1_1") (pintype "passive"))
      (node (ref "U23") (pin "4") (pinfunction "C2+_4") (pintype "passive"))
    )
    (net (code "36") (name "Net-(U23-C2-)") (class "Default")
      (node (ref "C123") (pin "2") (pinfunction "2_2") (pintype "passive"))
      (node (ref "U23") (pin "5") (pinfunction "C2-_5") (pintype "passive"))
    )
    (net (code "37") (name "Net-(U23-V+)") (class "Default")
      (node (ref "C124") (pin "1") (pinfunction "1_1") (pintype "passive"))
      (node (ref "U23") (pin "2") (pinfunction "V+_2") (pintype "passive"))
    )
    (net (code "38") (name "Net-(U23-V-)") (class "Default")
      (node (ref "C125") (pin "1") (pinfunction "1_1") (pintype "passive"))
      (node (ref "U23") (pin "6") (pinfunction "V-_6") (pintype "passive"))
    )
    (net (code "39") (name "Net-(U24-A)") (class "Default")
      (node (ref "L8") (pin "2") (pinfunction "2_2") (pintype "passive"))
      (node (ref "R164") (pin "2") (pinfunction "2_2") (pintype "passive"))
      (node (ref "U24") (pin "12") (pinfunction "A_12") (pintype "passive"))
    )
    (net (code "40") (name "Net-(U24-B)") (class "Default")
      (node (ref "L8") (pin "1") (pinfunction "1_1") (pintype "passive"))
      (node (ref "R165") (pin "1") (pinfunction "1_1") (pintype "passive"))
      (node (ref "U24") (pin "13") (pinfunction "B_13") (pintype "passive"))
    )
    (net (code "41") (name "Net-(U27-A)") (class "Default")
      (node (ref "L9") (pin "2") (pinfunction "2_2") (pintype "passive"))
      (node (ref "R168") (pin "2") (pinfunction "2_2") (pintype "passive"))
      (node (ref "U27") (pin "12") (pinfunction "A_12") (pintype "passive"))
    )
    (net (code "42") (name "Net-(U27-B)") (class "Default")
      (node (ref "L9") (pin "1") (pinfunction "1_1") (pintype "passive"))
      (node (ref "R169") (pin "1") (pinfunction "1_1") (pintype "passive"))
      (node (ref "U27") (pin "13") (pinfunction "B_13") (pintype "passive"))
    )
    (net (code "43") (name "VDD_3V3_MAIN") (class "Default")
      (node (ref "C118") (pin "2") (pinfunction "2_2") (pintype "passive"))
      (node (ref "C119") (pin "2") (pinfunction "2_2") (pintype "passive"))
      (node (ref "C121") (pin "1") (pinfunction "1_1") (pintype "passive"))
      (node (ref "C122") (pin "1") (pinfunction "1_1") (pintype "passive"))
      (node (ref "C132") (pin "1") (pinfunction "1_1") (pintype "passive"))
      (node (ref "C133") (pin "1") (pinfunction "1_1") (pintype "passive"))
      (node (ref "R163") (pin "1") (pinfunction "1_1") (pintype "passive"))
      (node (ref "R167") (pin "1") (pinfunction "1_1") (pintype "passive"))
      (node (ref "U23") (pin "16") (pinfunction "VCC_16") (pintype "passive"))
      (node (ref "U24") (pin "1") (pinfunction "Vcc1_1") (pintype "passive"))
      (node (ref "U27") (pin "1") (pinfunction "Vcc1_1") (pintype "passive"))
    )
    (net (code "44") (name "VDD_5V_ISO") (class "Default")
      (node (ref "C115") (pin "1") (pinfunction "1_1") (pintype "passive"))
      (node (ref "C116") (pin "1") (pinfunction "1_1") (pintype "passive"))
      (node (ref "MK1") (pin "4") (pinfunction "+Vo_4") (pintype "passive"))
      (node (ref "R164") (pin "1") (pinfunction "1_1") (pintype "passive"))
      (node (ref "R168") (pin "1") (pinfunction "1_1") (pintype "passive"))
      (node (ref "U24") (pin "16") (pinfunction "Vcc2_16") (pintype "passive"))
      (node (ref "U27") (pin "16") (pinfunction "Vcc2_16") (pintype "passive"))
    )
    (net (code "45") (name "VDD_5V_MAIN") (class "Default")
      (node (ref "C113") (pin "1") (pinfunction "1_1") (pintype "passive"))
      (node (ref "C114") (pin "1") (pinfunction "1_1") (pintype "passive"))
      (node (ref "MK1") (pin "2") (pinfunction "+Vin_2") (pintype "passive"))
    )
    (net (code "46") (name "VDD_12V_ISO") (class "Default")
      (node (ref "C111") (pin "1") (pinfunction "1_1") (pintype "passive"))
      (node (ref "C655") (pin "1") (pinfunction "1_1") (pintype "passive"))
      (node (ref "MK2") (pin "5") (pinfunction "+Vo_5") (pintype "passive"))
    )
    (net (code "47") (name "VDD_12V_MAIN") (class "Default")
      (node (ref "C109") (pin "1") (pinfunction "1_1") (pintype "passive"))
      (node (ref "C654") (pin "1") (pinfunction "1_1") (pintype "passive"))
      (node (ref "MK2") (pin "2") (pinfunction "+Vin_2") (pintype "passive"))
    )
    (net (code "48") (name "W32{slash}UART8_RX_M1{slash}3V3") (class "Default")
      (node (ref "U23") (pin "9") (pinfunction "R2out_9") (pintype "passive"))
    )
    (net (code "49") (name "Y32{slash}UART1_RX_M0{slash}3V3") (class "Default")
      (node (ref "R163") (pin "2") (pinfunction "2_2") (pintype "passive"))
      (node (ref "U24") (pin "3") (pinfunction "R_3") (pintype "passive"))
    )
    (net (code "50") (name "Y33{slash}UART8_TX_M1{slash}3V3") (class "Default")
      (node (ref "U23") (pin "10") (pinfunction "T2in_10") (pintype "passive"))
    )
    (net (code "51") (name "unconnected-(MK2-NC-Pad8)") (class "Default")
      (node (ref "MK2") (pin "8") (pinfunction "NC_8") (pintype "passive+no_connect"))
    )
    (net (code "52") (name "unconnected-(U24-NC-Pad11)") (class "Default")
      (node (ref "U24") (pin "11") (pinfunction "NC_11") (pintype "passive+no_connect"))
    )
    (net (code "53") (name "unconnected-(U24-NC1-Pad14)") (class "Default")
      (node (ref "U24") (pin "14") (pinfunction "NC1_14") (pintype "passive+no_connect"))
    )
    (net (code "54") (name "unconnected-(U27-NC-Pad11)") (class "Default")
      (node (ref "U27") (pin "11") (pinfunction "NC_11") (pintype "passive+no_connect"))
    )
    (net (code "55") (name "unconnected-(U27-NC1-Pad14)") (class "Default")
      (node (ref "U27") (pin "14") (pinfunction "NC1_14") (pintype "passive+no_connect"))
    )
  )
)
